# design.net
KiCad netlist of a schematic drawn in EAGLE
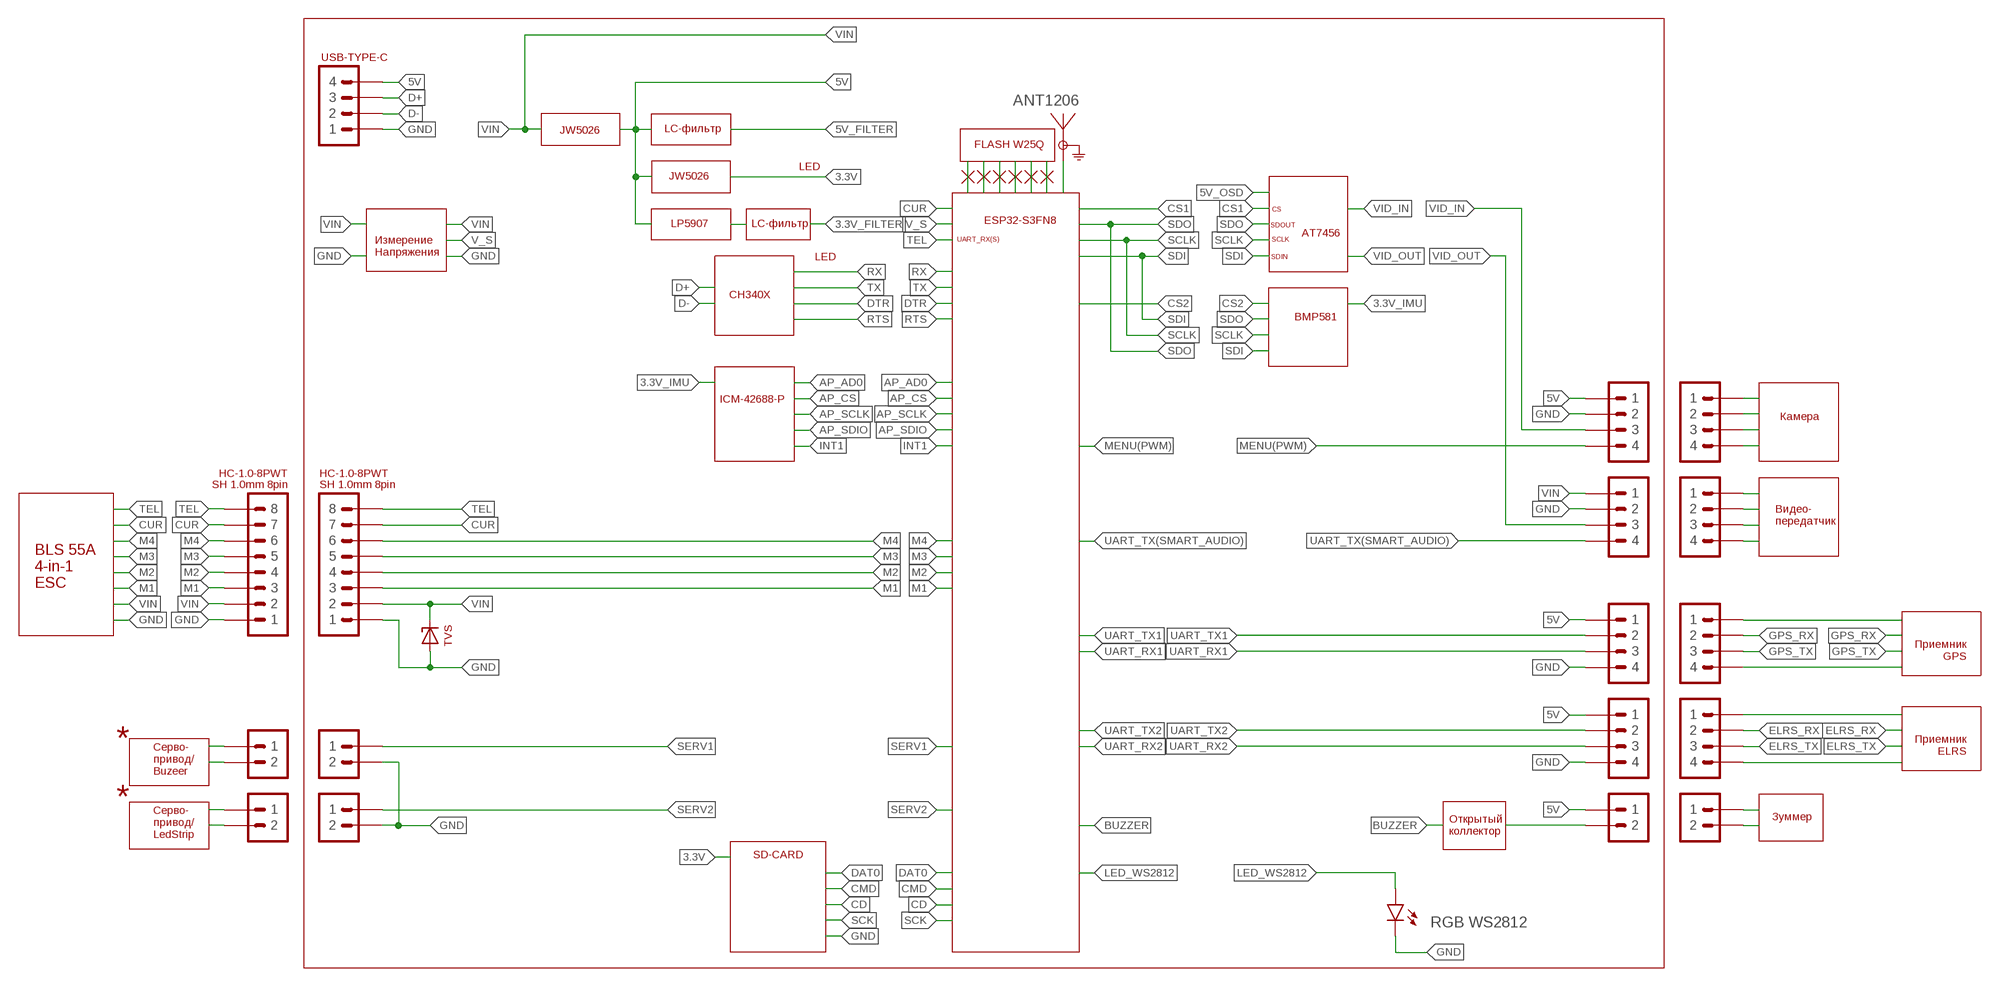
[diagram p0: schematic, sheet 1]

(export (version "E")
  (design (tool "Eeschema 10.0.6"))
  (components
    (comp (ref "LED2")
      (value "RGB WS2812")
      (footprint "eagle-import:2013")
      (libsource (lib "eagle-import") (part "LED2013"))
    )
    (comp (ref "U$2")
      (value "ANT1206")
      (footprint "eagle-import:1206")
      (libsource (lib "eagle-import") (part "ANT1206"))
    )
    (comp (ref "X1")
      (value "1X4JST-XH-04")
      (footprint "eagle-import:JST-XH-04")
      (libsource (lib "eagle-import") (part "1X4JST-XH-04"))
    )
    (comp (ref "X2")
      (value "1X4JST-XH-04")
      (footprint "eagle-import:JST-XH-04")
      (libsource (lib "eagle-import") (part "1X4JST-XH-04"))
    )
    (comp (ref "X3")
      (value "1X8JST-XH-08")
      (footprint "eagle-import:JST-XH-08")
      (libsource (lib "eagle-import") (part "1X8JST-XH-08"))
    )
    (comp (ref "X4")
      (value "1X4JST-XH-04")
      (footprint "eagle-import:JST-XH-04")
      (libsource (lib "eagle-import") (part "1X4JST-XH-04"))
    )
    (comp (ref "X5")
      (value "1X4JST-XH-04")
      (footprint "eagle-import:JST-XH-04")
      (libsource (lib "eagle-import") (part "1X4JST-XH-04"))
    )
    (comp (ref "X6")
      (value "1X4JST-XH-04")
      (footprint "eagle-import:JST-XH-04")
      (libsource (lib "eagle-import") (part "1X4JST-XH-04"))
    )
    (comp (ref "X7")
      (value "1X4JST-XH-04")
      (footprint "eagle-import:JST-XH-04")
      (libsource (lib "eagle-import") (part "1X4JST-XH-04"))
    )
    (comp (ref "X8")
      (value "1X4JST-XH-04")
      (footprint "eagle-import:JST-XH-04")
      (libsource (lib "eagle-import") (part "1X4JST-XH-04"))
    )
    (comp (ref "X9")
      (value "1X4JST-XH-04")
      (footprint "eagle-import:JST-XH-04")
      (libsource (lib "eagle-import") (part "1X4JST-XH-04"))
    )
    (comp (ref "X10")
      (value "1X4JST-XH-04")
      (footprint "eagle-import:JST-XH-04")
      (libsource (lib "eagle-import") (part "1X4JST-XH-04"))
    )
    (comp (ref "X11")
      (value "1X8JST-XH-08")
      (footprint "eagle-import:JST-XH-08")
      (libsource (lib "eagle-import") (part "1X8JST-XH-08"))
    )
    (comp (ref "X12")
      (value "1X2JST-XH-02")
      (footprint "eagle-import:JST-XH-02")
      (libsource (lib "eagle-import") (part "1X2JST-XH-02"))
    )
    (comp (ref "X13")
      (value "1X2JST-XH-02")
      (footprint "eagle-import:JST-XH-02")
      (libsource (lib "eagle-import") (part "1X2JST-XH-02"))
    )
    (comp (ref "X23")
      (value "1X2JST-XH-02")
      (footprint "eagle-import:JST-XH-02")
      (libsource (lib "eagle-import") (part "1X2JST-XH-02"))
    )
    (comp (ref "X24")
      (value "1X2JST-XH-02")
      (footprint "eagle-import:JST-XH-02")
      (libsource (lib "eagle-import") (part "1X2JST-XH-02"))
    )
    (comp (ref "X29")
      (value "1X2JST-XH-02")
      (footprint "eagle-import:JST-XH-02")
      (libsource (lib "eagle-import") (part "1X2JST-XH-02"))
    )
    (comp (ref "X30")
      (value "1X2JST-XH-02")
      (footprint "eagle-import:JST-XH-02")
      (libsource (lib "eagle-import") (part "1X2JST-XH-02"))
    )
    (comp (ref "ZD1")
      (value "ZENER-DIODESSOD123")
      (footprint "eagle-import:SOD123")
      (libsource (lib "eagle-import") (part "ZENER-DIODESSOD123"))
    )
  )
  (nets
    (net (code "1") (name "/DTR2") (class "Default")
      (node (ref "X4") (pin "1") (pinfunction "1_1") (pintype "passive"))
      (node (ref "X5") (pin "1") (pinfunction "1_1") (pintype "passive"))
    )
    (net (code "2") (name "/RX2") (class "Default")
      (node (ref "X4") (pin "4") (pinfunction "4_4") (pintype "passive"))
      (node (ref "X5") (pin "4") (pinfunction "4_4") (pintype "passive"))
    )
    (net (code "6") (name "5V") (class "Default")
      (node (ref "X1") (pin "1") (pinfunction "1_1") (pintype "passive"))
      (node (ref "X12") (pin "1") (pinfunction "1_1") (pintype "passive"))
      (node (ref "X2") (pin "1") (pinfunction "1_1") (pintype "passive"))
      (node (ref "X6") (pin "1") (pinfunction "1_1") (pintype "passive"))
      (node (ref "X9") (pin "4") (pinfunction "4_4") (pintype "passive"))
    )
    (net (code "18") (name "CUR") (class "Default")
      (node (ref "X11") (pin "7") (pinfunction "7_7") (pintype "passive"))
      (node (ref "X3") (pin "7") (pinfunction "7_7") (pintype "passive"))
    )
    (net (code "19") (name "D+") (class "Default")
      (node (ref "X9") (pin "3") (pinfunction "3_3") (pintype "passive"))
    )
    (net (code "20") (name "D-") (class "Default")
      (node (ref "X9") (pin "2") (pinfunction "2_2") (pintype "passive"))
    )
    (net (code "23") (name "ELRS_RX") (class "Default")
      (node (ref "X5") (pin "2") (pinfunction "2_2") (pintype "passive"))
    )
    (net (code "24") (name "ELRS_TX") (class "Default")
      (node (ref "X5") (pin "3") (pinfunction "3_3") (pintype "passive"))
    )
    (net (code "25") (name "GND") (class "Default")
      (node (ref "LED2") (pin "P$1") (pinfunction "C_P$1") (pintype "passive"))
      (node (ref "X1") (pin "4") (pinfunction "4_4") (pintype "passive"))
      (node (ref "X11") (pin "1") (pinfunction "1_1") (pintype "passive"))
      (node (ref "X2") (pin "4") (pinfunction "4_4") (pintype "passive"))
      (node (ref "X23") (pin "2") (pinfunction "2_2") (pintype "passive"))
      (node (ref "X24") (pin "2") (pinfunction "2_2") (pintype "passive"))
      (node (ref "X3") (pin "1") (pinfunction "1_1") (pintype "passive"))
      (node (ref "X6") (pin "2") (pinfunction "2_2") (pintype "passive"))
      (node (ref "X8") (pin "2") (pinfunction "2_2") (pintype "passive"))
      (node (ref "X9") (pin "1") (pinfunction "1_1") (pintype "passive"))
      (node (ref "ZD1") (pin "A") (pinfunction "A_A") (pintype "passive"))
    )
    (net (code "26") (name "GPS_RX") (class "Default")
      (node (ref "X4") (pin "2") (pinfunction "2_2") (pintype "passive"))
    )
    (net (code "27") (name "GPS_TX") (class "Default")
      (node (ref "X4") (pin "3") (pinfunction "3_3") (pintype "passive"))
    )
    (net (code "29") (name "LED_WS2812") (class "Default")
      (node (ref "LED2") (pin "P$2") (pinfunction "A_P$2") (pintype "passive"))
    )
    (net (code "30") (name "M1") (class "Default")
      (node (ref "X11") (pin "3") (pinfunction "3_3") (pintype "passive"))
      (node (ref "X3") (pin "3") (pinfunction "3_3") (pintype "passive"))
    )
    (net (code "31") (name "M2") (class "Default")
      (node (ref "X11") (pin "4") (pinfunction "4_4") (pintype "passive"))
      (node (ref "X3") (pin "4") (pinfunction "4_4") (pintype "passive"))
    )
    (net (code "32") (name "M3") (class "Default")
      (node (ref "X11") (pin "5") (pinfunction "5_5") (pintype "passive"))
      (node (ref "X3") (pin "5") (pinfunction "5_5") (pintype "passive"))
    )
    (net (code "33") (name "M4") (class "Default")
      (node (ref "X11") (pin "6") (pinfunction "6_6") (pintype "passive"))
      (node (ref "X3") (pin "6") (pinfunction "6_6") (pintype "passive"))
    )
    (net (code "34") (name "MENU(PWM)") (class "Default")
      (node (ref "X6") (pin "4") (pinfunction "4_4") (pintype "passive"))
    )
    (net (code "41") (name "SERV1") (class "Default")
      (node (ref "X23") (pin "1") (pinfunction "1_1") (pintype "passive"))
    )
    (net (code "42") (name "SERV2") (class "Default")
      (node (ref "X24") (pin "1") (pinfunction "1_1") (pintype "passive"))
    )
    (net (code "43") (name "TEL") (class "Default")
      (node (ref "X11") (pin "8") (pinfunction "8_8") (pintype "passive"))
      (node (ref "X3") (pin "8") (pinfunction "8_8") (pintype "passive"))
    )
    (net (code "45") (name "UART_RX1") (class "Default")
      (node (ref "X1") (pin "3") (pinfunction "3_3") (pintype "passive"))
    )
    (net (code "46") (name "UART_RX2") (class "Default")
      (node (ref "X2") (pin "3") (pinfunction "3_3") (pintype "passive"))
    )
    (net (code "47") (name "UART_TX(SMART_AUDIO)") (class "Default")
      (node (ref "X8") (pin "4") (pinfunction "4_4") (pintype "passive"))
    )
    (net (code "48") (name "UART_TX1") (class "Default")
      (node (ref "X1") (pin "2") (pinfunction "2_2") (pintype "passive"))
    )
    (net (code "49") (name "UART_TX2") (class "Default")
      (node (ref "X2") (pin "2") (pinfunction "2_2") (pintype "passive"))
    )
    (net (code "50") (name "VID_IN") (class "Default")
      (node (ref "X6") (pin "3") (pinfunction "3_3") (pintype "passive"))
    )
    (net (code "51") (name "VID_OUT") (class "Default")
      (node (ref "X8") (pin "3") (pinfunction "3_3") (pintype "passive"))
    )
    (net (code "52") (name "VIN") (class "Default")
      (node (ref "X11") (pin "2") (pinfunction "2_2") (pintype "passive"))
      (node (ref "X3") (pin "2") (pinfunction "2_2") (pintype "passive"))
      (node (ref "X8") (pin "1") (pinfunction "1_1") (pintype "passive"))
      (node (ref "ZD1") (pin "C") (pinfunction "C_C") (pintype "passive"))
    )
    (net (code "54") (name "unconnected-(U$2-ANT-Pad1)") (class "Default")
      (node (ref "U$2") (pin "1") (pinfunction "ANT_1") (pintype "bidirectional"))
    )
    (net (code "55") (name "unconnected-(U$2-GND-Pad2)") (class "Default")
      (node (ref "U$2") (pin "2") (pinfunction "GND_2") (pintype "bidirectional"))
    )
    (net (code "56") (name "unconnected-(X7-Pad1)") (class "Default")
      (node (ref "X7") (pin "1") (pinfunction "1_1") (pintype "passive"))
    )
    (net (code "57") (name "unconnected-(X7-Pad2)") (class "Default")
      (node (ref "X7") (pin "2") (pinfunction "2_2") (pintype "passive"))
    )
    (net (code "58") (name "unconnected-(X7-Pad3)") (class "Default")
      (node (ref "X7") (pin "3") (pinfunction "3_3") (pintype "passive"))
    )
    (net (code "59") (name "unconnected-(X7-Pad4)") (class "Default")
      (node (ref "X7") (pin "4") (pinfunction "4_4") (pintype "passive"))
    )
    (net (code "60") (name "unconnected-(X10-Pad1)") (class "Default")
      (node (ref "X10") (pin "1") (pinfunction "1_1") (pintype "passive"))
    )
    (net (code "61") (name "unconnected-(X10-Pad2)") (class "Default")
      (node (ref "X10") (pin "2") (pinfunction "2_2") (pintype "passive"))
    )
    (net (code "62") (name "unconnected-(X10-Pad3)") (class "Default")
      (node (ref "X10") (pin "3") (pinfunction "3_3") (pintype "passive"))
    )
    (net (code "63") (name "unconnected-(X10-Pad4)") (class "Default")
      (node (ref "X10") (pin "4") (pinfunction "4_4") (pintype "passive"))
    )
    (net (code "64") (name "unconnected-(X12-Pad2)") (class "Default")
      (node (ref "X12") (pin "2") (pinfunction "2_2") (pintype "passive"))
    )
    (net (code "65") (name "unconnected-(X13-Pad1)") (class "Default")
      (node (ref "X13") (pin "1") (pinfunction "1_1") (pintype "passive"))
    )
    (net (code "66") (name "unconnected-(X13-Pad2)") (class "Default")
      (node (ref "X13") (pin "2") (pinfunction "2_2") (pintype "passive"))
    )
    (net (code "67") (name "unconnected-(X29-Pad1)") (class "Default")
      (node (ref "X29") (pin "1") (pinfunction "1_1") (pintype "passive"))
    )
    (net (code "68") (name "unconnected-(X29-Pad2)") (class "Default")
      (node (ref "X29") (pin "2") (pinfunction "2_2") (pintype "passive"))
    )
    (net (code "69") (name "unconnected-(X30-Pad1)") (class "Default")
      (node (ref "X30") (pin "1") (pinfunction "1_1") (pintype "passive"))
    )
    (net (code "70") (name "unconnected-(X30-Pad2)") (class "Default")
      (node (ref "X30") (pin "2") (pinfunction "2_2") (pintype "passive"))
    )
  )
)
